# cannaster.net
KiCad netlist of a schematic drawn in EAGLE
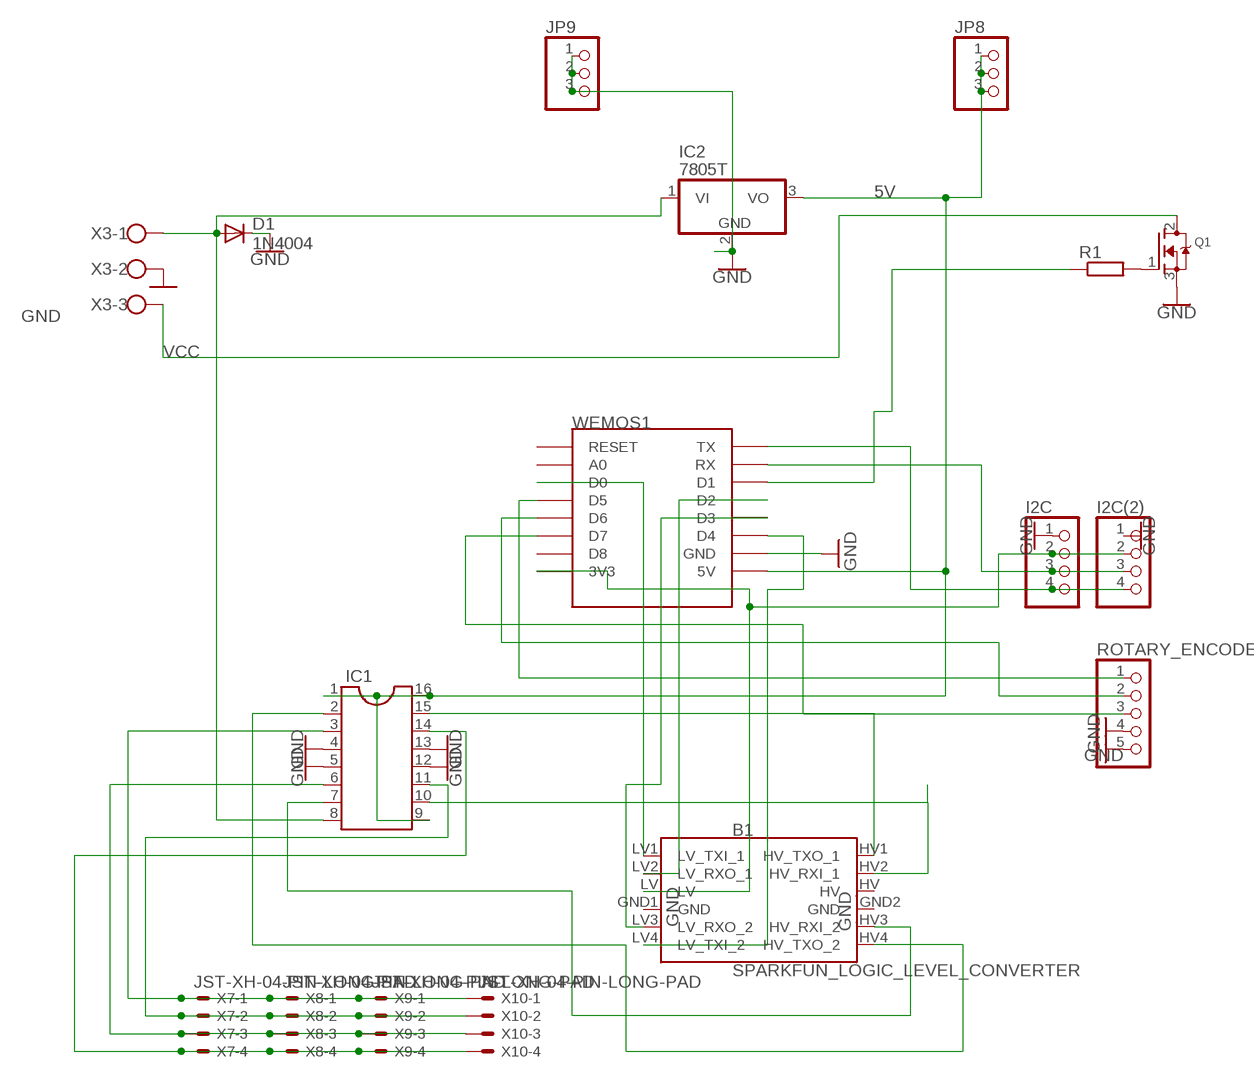
[diagram p0: schematic, sheet 1]

(export (version "E")
  (design (tool "Eeschema 10.0.6"))
  (components
    (comp (ref "B1")
      (value "SPARKFUN_LOGIC_LEVEL_CONVERTER")
      (footprint "eagle-import:SPARKFUN_LOGIC_LEVEL_CONVERTER")
      (libsource (lib "eagle-import") (part "SPARKFUN_LOGIC_LEVEL_CONVERTER"))
    )
    (comp (ref "D1")
      (value "1N4004")
      (footprint "eagle-import:DO41-10")
      (libsource (lib "eagle-import") (part "1N4004"))
    )
    (comp (ref "I2C")
      (value "PINHD-1X4")
      (footprint "eagle-import:1X04")
      (libsource (lib "eagle-import") (part "PINHD-1X4"))
    )
    (comp (ref "I2C(2)")
      (value "PINHD-1X4")
      (footprint "eagle-import:1X04")
      (libsource (lib "eagle-import") (part "PINHD-1X4"))
    )
    (comp (ref "IC1")
      (value "DIL16")
      (footprint "eagle-import:DIL16")
      (libsource (lib "eagle-import") (part "DIL16"))
    )
    (comp (ref "IC2")
      (value "7805T")
      (footprint "eagle-import:TO220H")
      (libsource (lib "eagle-import") (part "78T05"))
    )
    (comp (ref "JP8")
      (value "PINHD-1X3")
      (footprint "eagle-import:1X03")
      (libsource (lib "eagle-import") (part "PINHD-1X3"))
    )
    (comp (ref "JP9")
      (value "PINHD-1X3")
      (footprint "eagle-import:1X03")
      (libsource (lib "eagle-import") (part "PINHD-1X3"))
    )
    (comp (ref "Q1")
      (value "MOSFET-NGDS_TO220V")
      (footprint "eagle-import:TO220V")
      (libsource (lib "eagle-import") (part "MOSFET-NGDS_TO220V"))
    )
    (comp (ref "R1")
      (value "R-EU_0207/7")
      (footprint "eagle-import:0207_7")
      (libsource (lib "eagle-import") (part "R-EU_0207/7"))
    )
    (comp (ref "ROTARY_ENCODER")
      (value "PINHD-1X5")
      (footprint "eagle-import:1X05")
      (libsource (lib "eagle-import") (part "PINHD-1X5"))
    )
    (comp (ref "WEMOS1")
      (value "WEMOS-D1-MINI")
      (footprint "eagle-import:WEMOS-D1-MINI")
      (libsource (lib "eagle-import") (part "WEMOS-D1-MINI"))
    )
    (comp (ref "X3")
      (value "W237-103")
      (footprint "eagle-import:W237-103")
      (fields (field (name "MPN") "237-103"))
      (libsource (lib "eagle-import") (part "W237-103"))
    )
    (comp (ref "X7")
      (value "JST-XH-04-PIN-LONG-PAD")
      (footprint "eagle-import:JST-XH-04-PACKAGE-LONG-PAD")
      (libsource (lib "eagle-import") (part "JST-XH-04-PIN-LONG-PAD"))
    )
    (comp (ref "X8")
      (value "JST-XH-04-PIN-LONG-PAD")
      (footprint "eagle-import:JST-XH-04-PACKAGE-LONG-PAD")
      (libsource (lib "eagle-import") (part "JST-XH-04-PIN-LONG-PAD"))
    )
    (comp (ref "X9")
      (value "JST-XH-04-PIN-LONG-PAD")
      (footprint "eagle-import:JST-XH-04-PACKAGE-LONG-PAD")
      (libsource (lib "eagle-import") (part "JST-XH-04-PIN-LONG-PAD"))
    )
    (comp (ref "X10")
      (value "JST-XH-04-PIN-LONG-PAD")
      (footprint "eagle-import:JST-XH-04-PACKAGE-LONG-PAD")
      (libsource (lib "eagle-import") (part "JST-XH-04-PIN-LONG-PAD"))
    )
  )
  (nets
    (net (code "1") (name "/5V") (class "Default")
      (node (ref "IC1") (pin "1") (pinfunction "1_1") (pintype "passive"))
      (node (ref "IC1") (pin "16") (pinfunction "16_16") (pintype "passive"))
      (node (ref "IC1") (pin "9") (pinfunction "9_9") (pintype "passive"))
      (node (ref "IC2") (pin "3") (pinfunction "VO_3") (pintype "passive"))
      (node (ref "JP8") (pin "1") (pinfunction "1_1") (pintype "passive"))
      (node (ref "JP8") (pin "2") (pinfunction "2_2") (pintype "passive"))
      (node (ref "JP8") (pin "3") (pinfunction "3_3") (pintype "passive"))
      (node (ref "WEMOS1") (pin "5V") (pinfunction "5V_5V") (pintype "bidirectional"))
    )
    (net (code "2") (name "/HV") (class "Default")
      (node (ref "B1") (pin "HV") (pinfunction "HV_HV") (pintype "power_in"))
    )
    (net (code "3") (name "/VCC") (class "Default")
      (node (ref "D1") (pin "A") (pinfunction "A_A") (pintype "passive"))
      (node (ref "IC1") (pin "8") (pinfunction "8_8") (pintype "passive"))
      (node (ref "IC2") (pin "1") (pinfunction "VI_1") (pintype "input"))
      (node (ref "X3") (pin "1") (pinfunction "KL_1") (pintype "passive"))
    )
    (net (code "4") (name "GND") (class "Default")
      (node (ref "B1") (pin "GND1") (pinfunction "GND_GND1") (pintype "power_in"))
      (node (ref "B1") (pin "GND2") (pinfunction "GND_GND2") (pintype "power_in"))
      (node (ref "D1") (pin "C") (pinfunction "C_C") (pintype "passive"))
      (node (ref "I2C") (pin "1") (pinfunction "1_1") (pintype "passive"))
      (node (ref "I2C(2)") (pin "1") (pinfunction "1_1") (pintype "passive"))
      (node (ref "IC1") (pin "12") (pinfunction "12_12") (pintype "passive"))
      (node (ref "IC1") (pin "13") (pinfunction "13_13") (pintype "passive"))
      (node (ref "IC1") (pin "4") (pinfunction "4_4") (pintype "passive"))
      (node (ref "IC1") (pin "5") (pinfunction "5_5") (pintype "passive"))
      (node (ref "IC2") (pin "2") (pinfunction "GND_2") (pintype "passive"))
      (node (ref "JP9") (pin "1") (pinfunction "1_1") (pintype "passive"))
      (node (ref "JP9") (pin "2") (pinfunction "2_2") (pintype "passive"))
      (node (ref "JP9") (pin "3") (pinfunction "3_3") (pintype "passive"))
      (node (ref "Q1") (pin "3") (pinfunction "S_3") (pintype "bidirectional"))
      (node (ref "ROTARY_ENCODER") (pin "4") (pinfunction "4_4") (pintype "passive"))
      (node (ref "ROTARY_ENCODER") (pin "5") (pinfunction "5_5") (pintype "passive"))
      (node (ref "WEMOS1") (pin "GND") (pinfunction "GND_GND") (pintype "bidirectional"))
      (node (ref "X3") (pin "2") (pinfunction "KL_2") (pintype "passive"))
    )
    (net (code "5") (name "Net-(B1-HV_RXI_1)") (class "Default")
      (node (ref "B1") (pin "HV2") (pinfunction "HV_RXI_1_HV2") (pintype "bidirectional"))
      (node (ref "IC1") (pin "10") (pinfunction "10_10") (pintype "passive"))
    )
    (net (code "6") (name "Net-(B1-HV_RXI_2)") (class "Default")
      (node (ref "B1") (pin "HV3") (pinfunction "HV_RXI_2_HV3") (pintype "bidirectional"))
      (node (ref "IC1") (pin "7") (pinfunction "7_7") (pintype "passive"))
    )
    (net (code "7") (name "Net-(B1-HV_TXO_1)") (class "Default")
      (node (ref "B1") (pin "HV1") (pinfunction "HV_TXO_1_HV1") (pintype "bidirectional"))
      (node (ref "IC1") (pin "15") (pinfunction "15_15") (pintype "passive"))
    )
    (net (code "8") (name "Net-(B1-HV_TXO_2)") (class "Default")
      (node (ref "B1") (pin "HV4") (pinfunction "HV_TXO_2_HV4") (pintype "bidirectional"))
      (node (ref "IC1") (pin "2") (pinfunction "2_2") (pintype "passive"))
    )
    (net (code "9") (name "Net-(B1-LV_RXO_1)") (class "Default")
      (node (ref "B1") (pin "LV2") (pinfunction "LV_RXO_1_LV2") (pintype "bidirectional"))
      (node (ref "WEMOS1") (pin "D2") (pinfunction "D2_D2") (pintype "bidirectional"))
    )
    (net (code "10") (name "Net-(B1-LV_RXO_2)") (class "Default")
      (node (ref "B1") (pin "LV3") (pinfunction "LV_RXO_2_LV3") (pintype "bidirectional"))
      (node (ref "WEMOS1") (pin "D3") (pinfunction "D3_D3") (pintype "bidirectional"))
    )
    (net (code "11") (name "Net-(B1-LV_TXI_1)") (class "Default")
      (node (ref "B1") (pin "LV1") (pinfunction "LV_TXI_1_LV1") (pintype "bidirectional"))
      (node (ref "WEMOS1") (pin "D0") (pinfunction "D0_D0") (pintype "bidirectional"))
    )
    (net (code "12") (name "Net-(B1-LV_TXI_2)") (class "Default")
      (node (ref "B1") (pin "LV4") (pinfunction "LV_TXI_2_LV4") (pintype "bidirectional"))
      (node (ref "WEMOS1") (pin "D4") (pinfunction "D4_D4") (pintype "bidirectional"))
    )
    (net (code "13") (name "Net-(B1-PadLV)") (class "Default")
      (node (ref "B1") (pin "LV") (pinfunction "LV_LV") (pintype "power_in"))
      (node (ref "I2C") (pin "2") (pinfunction "2_2") (pintype "passive"))
      (node (ref "I2C(2)") (pin "2") (pinfunction "2_2") (pintype "passive"))
      (node (ref "WEMOS1") (pin "3V3") (pinfunction "3V3_3V3") (pintype "bidirectional"))
    )
    (net (code "14") (name "Net-(I2C(2)-Pad3)") (class "Default")
      (node (ref "I2C") (pin "3") (pinfunction "3_3") (pintype "passive"))
      (node (ref "I2C(2)") (pin "3") (pinfunction "3_3") (pintype "passive"))
      (node (ref "WEMOS1") (pin "RX") (pinfunction "RX_RX") (pintype "bidirectional"))
    )
    (net (code "15") (name "Net-(I2C(2)-Pad4)") (class "Default")
      (node (ref "I2C") (pin "4") (pinfunction "4_4") (pintype "passive"))
      (node (ref "I2C(2)") (pin "4") (pinfunction "4_4") (pintype "passive"))
      (node (ref "WEMOS1") (pin "TX") (pinfunction "TX_TX") (pintype "bidirectional"))
    )
    (net (code "16") (name "Net-(Q1-D)") (class "Default")
      (node (ref "Q1") (pin "2") (pinfunction "D_2") (pintype "bidirectional"))
      (node (ref "X3") (pin "3") (pinfunction "KL_3") (pintype "passive"))
    )
    (net (code "17") (name "Net-(Q1-G)") (class "Default")
      (node (ref "Q1") (pin "1") (pinfunction "G_1") (pintype "bidirectional"))
      (node (ref "R1") (pin "2") (pinfunction "2_2") (pintype "passive"))
    )
    (net (code "18") (name "Net-(R1-Pad1)") (class "Default")
      (node (ref "R1") (pin "1") (pinfunction "1_1") (pintype "passive"))
      (node (ref "WEMOS1") (pin "D1") (pinfunction "D1_D1") (pintype "bidirectional"))
    )
    (net (code "19") (name "Net-(ROTARY_ENCODER-Pad1)") (class "Default")
      (node (ref "ROTARY_ENCODER") (pin "1") (pinfunction "1_1") (pintype "passive"))
      (node (ref "WEMOS1") (pin "D5") (pinfunction "D5_D5") (pintype "bidirectional"))
    )
    (net (code "20") (name "Net-(ROTARY_ENCODER-Pad2)") (class "Default")
      (node (ref "ROTARY_ENCODER") (pin "2") (pinfunction "2_2") (pintype "passive"))
      (node (ref "WEMOS1") (pin "D6") (pinfunction "D6_D6") (pintype "bidirectional"))
    )
    (net (code "21") (name "Net-(ROTARY_ENCODER-Pad3)") (class "Default")
      (node (ref "ROTARY_ENCODER") (pin "3") (pinfunction "3_3") (pintype "passive"))
      (node (ref "WEMOS1") (pin "D7") (pinfunction "D7_D7") (pintype "bidirectional"))
    )
    (net (code "22") (name "Net-(X10A-S)") (class "Default")
      (node (ref "IC1") (pin "3") (pinfunction "3_3") (pintype "passive"))
      (node (ref "X10") (pin "1") (pinfunction "S_1") (pintype "passive"))
      (node (ref "X7") (pin "1") (pinfunction "S_1") (pintype "passive"))
      (node (ref "X8") (pin "1") (pinfunction "S_1") (pintype "passive"))
      (node (ref "X9") (pin "1") (pinfunction "S_1") (pintype "passive"))
    )
    (net (code "23") (name "Net-(X10B-S)") (class "Default")
      (node (ref "IC1") (pin "11") (pinfunction "11_11") (pintype "passive"))
      (node (ref "X10") (pin "2") (pinfunction "S_2") (pintype "passive"))
      (node (ref "X7") (pin "2") (pinfunction "S_2") (pintype "passive"))
      (node (ref "X8") (pin "2") (pinfunction "S_2") (pintype "passive"))
      (node (ref "X9") (pin "2") (pinfunction "S_2") (pintype "passive"))
    )
    (net (code "24") (name "Net-(X10C-S)") (class "Default")
      (node (ref "IC1") (pin "6") (pinfunction "6_6") (pintype "passive"))
      (node (ref "X10") (pin "3") (pinfunction "S_3") (pintype "passive"))
      (node (ref "X7") (pin "3") (pinfunction "S_3") (pintype "passive"))
      (node (ref "X8") (pin "3") (pinfunction "S_3") (pintype "passive"))
      (node (ref "X9") (pin "3") (pinfunction "S_3") (pintype "passive"))
    )
    (net (code "25") (name "Net-(X10D-S)") (class "Default")
      (node (ref "IC1") (pin "14") (pinfunction "14_14") (pintype "passive"))
      (node (ref "X10") (pin "4") (pinfunction "S_4") (pintype "passive"))
      (node (ref "X7") (pin "4") (pinfunction "S_4") (pintype "passive"))
      (node (ref "X8") (pin "4") (pinfunction "S_4") (pintype "passive"))
      (node (ref "X9") (pin "4") (pinfunction "S_4") (pintype "passive"))
    )
    (net (code "26") (name "unconnected-(WEMOS1-PadA0)") (class "Default")
      (node (ref "WEMOS1") (pin "A0") (pinfunction "A0_A0") (pintype "bidirectional"))
    )
    (net (code "27") (name "unconnected-(WEMOS1-PadD8)") (class "Default")
      (node (ref "WEMOS1") (pin "D8") (pinfunction "D8_D8") (pintype "bidirectional"))
    )
    (net (code "28") (name "unconnected-(WEMOS1-PadRESET)") (class "Default")
      (node (ref "WEMOS1") (pin "RESET") (pinfunction "RESET_RESET") (pintype "bidirectional"))
    )
  )
)
